# nrf52840-breakout-mdbt50q.net
KiCad netlist of a schematic drawn in EAGLE
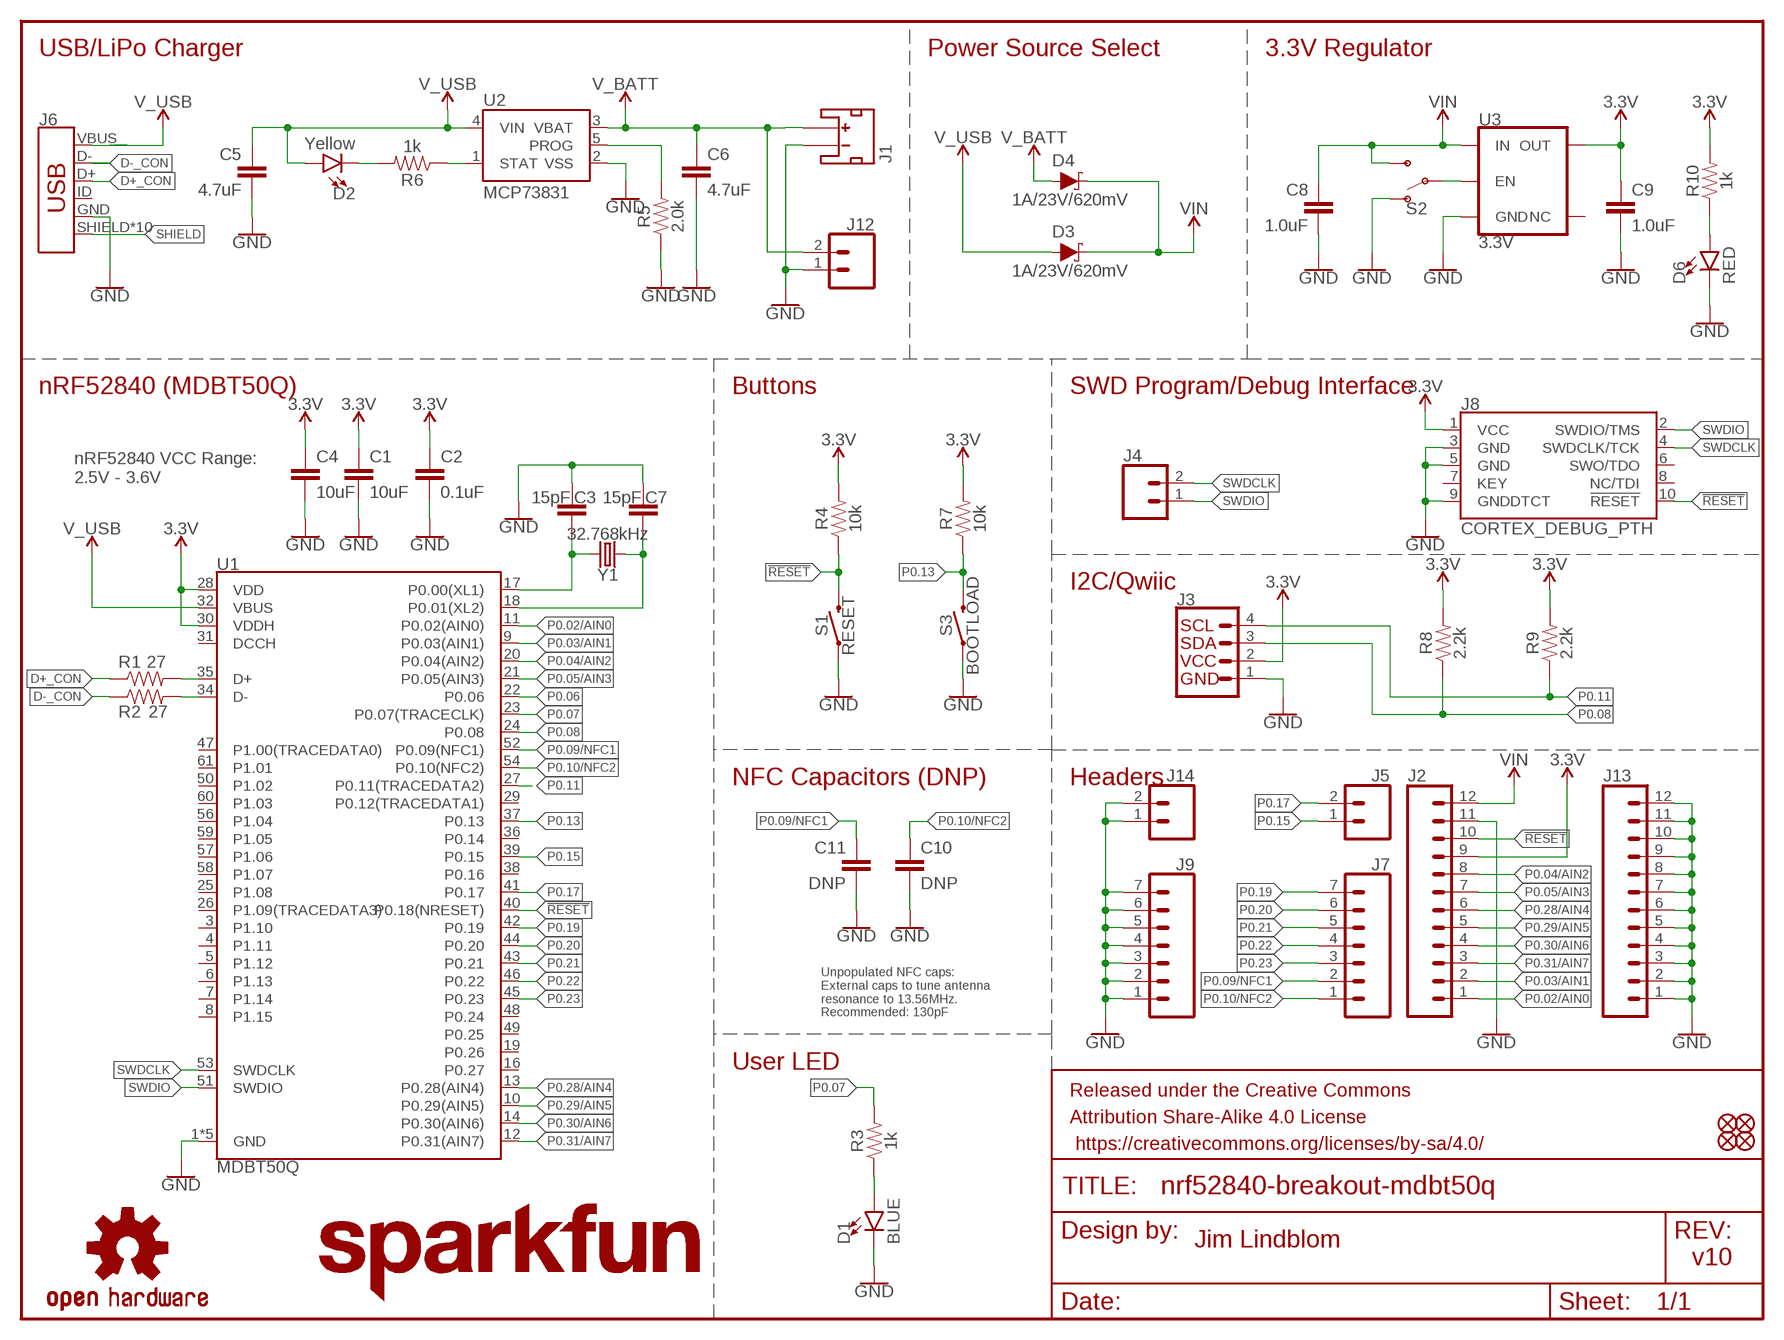
[diagram p0: schematic, sheet 1]

(export (version "E")
  (design (tool "Eeschema 10.0.6"))
  (components
    (comp (ref "C1")
      (value "10uF")
      (footprint "eagle-import:0603")
      (libsource (lib "eagle-import") (part "10UF-0603-6.3V-20%"))
    )
    (comp (ref "C2")
      (value "0.1uF")
      (footprint "eagle-import:0603")
      (libsource (lib "eagle-import") (part "0.1UF-0603-25V-(+80/-20%)"))
    )
    (comp (ref "C3")
      (value "15pF")
      (footprint "eagle-import:0603")
      (libsource (lib "eagle-import") (part "15PF-0603-50V-5%"))
    )
    (comp (ref "C4")
      (value "10uF")
      (footprint "eagle-import:0603")
      (libsource (lib "eagle-import") (part "10UF-0603-6.3V-20%"))
    )
    (comp (ref "C5")
      (value "4.7uF")
      (footprint "eagle-import:0603")
      (libsource (lib "eagle-import") (part "4.7UF-0603-6.3V-(10%)"))
    )
    (comp (ref "C6")
      (value "4.7uF")
      (footprint "eagle-import:0603")
      (libsource (lib "eagle-import") (part "4.7UF-0603-6.3V-(10%)"))
    )
    (comp (ref "C7")
      (value "15pF")
      (footprint "eagle-import:0603")
      (libsource (lib "eagle-import") (part "15PF-0603-50V-5%"))
    )
    (comp (ref "C8")
      (value "1.0uF")
      (footprint "eagle-import:0603")
      (libsource (lib "eagle-import") (part "1.0UF-0603-16V-10%"))
    )
    (comp (ref "C9")
      (value "1.0uF")
      (footprint "eagle-import:0603")
      (libsource (lib "eagle-import") (part "1.0UF-0603-16V-10%"))
    )
    (comp (ref "C10")
      (value "DNP")
      (footprint "eagle-import:0603")
      (libsource (lib "eagle-import") (part "270PF-0603-50V-5%"))
    )
    (comp (ref "C11")
      (value "DNP")
      (footprint "eagle-import:0603")
      (libsource (lib "eagle-import") (part "270PF-0603-50V-5%"))
    )
    (comp (ref "D1")
      (value "BLUE")
      (footprint "eagle-import:LED-0603")
      (libsource (lib "eagle-import") (part "LED-BLUE0603"))
    )
    (comp (ref "D2")
      (value "Yellow")
      (footprint "eagle-import:LED-0603")
      (libsource (lib "eagle-import") (part "LED-YELLOW0603"))
    )
    (comp (ref "D3")
      (value "1A/23V/620mV")
      (footprint "eagle-import:SOD-323")
      (libsource (lib "eagle-import") (part "DIODE-SCHOTTKY-BAT20J"))
    )
    (comp (ref "D4")
      (value "1A/23V/620mV")
      (footprint "eagle-import:SOD-323")
      (libsource (lib "eagle-import") (part "DIODE-SCHOTTKY-BAT20J"))
    )
    (comp (ref "D6")
      (value "RED")
      (footprint "eagle-import:LED-0603")
      (libsource (lib "eagle-import") (part "LED-RED0603"))
    )
    (comp (ref "FD1")
      (value "FIDUCIALUFIDUCIAL")
      (footprint "eagle-import:FIDUCIAL-MICRO")
      (libsource (lib "eagle-import") (part "FIDUCIALUFIDUCIAL"))
    )
    (comp (ref "FD2")
      (value "FIDUCIALUFIDUCIAL")
      (footprint "eagle-import:FIDUCIAL-MICRO")
      (libsource (lib "eagle-import") (part "FIDUCIALUFIDUCIAL"))
    )
    (comp (ref "FD3")
      (value "FIDUCIALUFIDUCIAL")
      (footprint "eagle-import:FIDUCIAL-MICRO")
      (libsource (lib "eagle-import") (part "FIDUCIALUFIDUCIAL"))
    )
    (comp (ref "FD4")
      (value "FIDUCIALUFIDUCIAL")
      (footprint "eagle-import:FIDUCIAL-MICRO")
      (libsource (lib "eagle-import") (part "FIDUCIALUFIDUCIAL"))
    )
    (comp (ref "FRAME1")
      (value "FRAME-LETTER")
      (footprint "eagle-import:CREATIVE_COMMONS")
      (libsource (lib "eagle-import") (part "FRAME-LETTER"))
    )
    (comp (ref "J1")
      (value "JST_2MM_MALESMD")
      (footprint "eagle-import:JST-2-SMD")
      (libsource (lib "eagle-import") (part "JST_2MM_MALESMD"))
    )
    (comp (ref "J2")
      (value "CONN_12NO_SILK")
      (footprint "eagle-import:1X12_NO_SILK")
      (libsource (lib "eagle-import") (part "CONN_12NO_SILK"))
    )
    (comp (ref "J3")
      (value "QWIIC_CONNECTORJS-1MM")
      (footprint "eagle-import:1X04_1MM_RA")
      (libsource (lib "eagle-import") (part "QWIIC_CONNECTORJS-1MM"))
    )
    (comp (ref "J4")
      (value "CONN_021X02_NO_SILK")
      (footprint "eagle-import:1X02_NO_SILK")
      (libsource (lib "eagle-import") (part "CONN_021X02_NO_SILK"))
    )
    (comp (ref "J5")
      (value "CONN_021X02_NO_SILK")
      (footprint "eagle-import:1X02_NO_SILK")
      (libsource (lib "eagle-import") (part "CONN_021X02_NO_SILK"))
    )
    (comp (ref "J6")
      (value "USB_MICRO-B_HALF_PTH_MILL")
      (footprint "eagle-import:USB-MICROB-PTH-MILL")
      (libsource (lib "eagle-import") (part "USB_MICRO-B_HALF_PTH_MILL"))
    )
    (comp (ref "J7")
      (value "CONN_07NO_SILK")
      (footprint "eagle-import:1X07_NO_SILK")
      (libsource (lib "eagle-import") (part "CONN_07NO_SILK"))
    )
    (comp (ref "J8")
      (value "CORTEX_DEBUG_PTH")
      (footprint "eagle-import:2X5-PTH-1.27MM")
      (libsource (lib "eagle-import") (part "CORTEX_DEBUG_PTH"))
    )
    (comp (ref "J9")
      (value "CONN_07NO_SILK")
      (footprint "eagle-import:1X07_NO_SILK")
      (libsource (lib "eagle-import") (part "CONN_07NO_SILK"))
    )
    (comp (ref "J12")
      (value "CONN_021X02_NO_SILK")
      (footprint "eagle-import:1X02_NO_SILK")
      (libsource (lib "eagle-import") (part "CONN_021X02_NO_SILK"))
    )
    (comp (ref "J13")
      (value "CONN_12NO_SILK")
      (footprint "eagle-import:1X12_NO_SILK")
      (libsource (lib "eagle-import") (part "CONN_12NO_SILK"))
    )
    (comp (ref "J14")
      (value "CONN_021X02_NO_SILK")
      (footprint "eagle-import:1X02_NO_SILK")
      (libsource (lib "eagle-import") (part "CONN_021X02_NO_SILK"))
    )
    (comp (ref "LOGO1")
      (value "SFE_LOGO_NAME.2_INCH")
      (footprint "eagle-import:SFE_LOGO_NAME_.2")
      (libsource (lib "eagle-import") (part "SFE_LOGO_NAME.2_INCH"))
    )
    (comp (ref "LOGO2")
      (value "OSHW-LOGOS")
      (footprint "eagle-import:OSHW-LOGO-S")
      (libsource (lib "eagle-import") (part "OSHW-LOGOS"))
    )
    (comp (ref "R1")
      (value "27")
      (footprint "eagle-import:0603")
      (libsource (lib "eagle-import") (part "27OHM-0603-1/10W-1%"))
    )
    (comp (ref "R2")
      (value "27")
      (footprint "eagle-import:0603")
      (libsource (lib "eagle-import") (part "27OHM-0603-1/10W-1%"))
    )
    (comp (ref "R3")
      (value "1k")
      (footprint "eagle-import:0603")
      (libsource (lib "eagle-import") (part "1KOHM-0603-1/10W-1%"))
    )
    (comp (ref "R4")
      (value "10k")
      (footprint "eagle-import:0603")
      (libsource (lib "eagle-import") (part "10KOHM-0603-1/10W-1%"))
    )
    (comp (ref "R5")
      (value "2.0k")
      (footprint "eagle-import:0603")
      (libsource (lib "eagle-import") (part "2.0KOHM-0603-1/10W-5%"))
    )
    (comp (ref "R6")
      (value "1k")
      (footprint "eagle-import:0603")
      (libsource (lib "eagle-import") (part "1KOHM-0603-1/10W-1%"))
    )
    (comp (ref "R7")
      (value "10k")
      (footprint "eagle-import:0603")
      (libsource (lib "eagle-import") (part "10KOHM-0603-1/10W-1%"))
    )
    (comp (ref "R8")
      (value "2.2k")
      (footprint "eagle-import:0603")
      (libsource (lib "eagle-import") (part "2.2KOHM-0603-1/10W-1%"))
    )
    (comp (ref "R9")
      (value "2.2k")
      (footprint "eagle-import:0603")
      (libsource (lib "eagle-import") (part "2.2KOHM-0603-1/10W-1%"))
    )
    (comp (ref "R10")
      (value "1k")
      (footprint "eagle-import:0603")
      (libsource (lib "eagle-import") (part "1KOHM-0603-1/10W-1%"))
    )
    (comp (ref "S1")
      (value "RESET")
      (footprint "eagle-import:TACTILE_SWITCH_SMD_RIGHT_ANGLE")
      (libsource (lib "eagle-import") (part "MOMENTARY-SWITCH-SPST-SMD-RIGHT-ANGLE"))
    )
    (comp (ref "S2")
      (value "SWITCH-SPDT-SMD-RIGHT-ANGLE")
      (footprint "eagle-import:SWITCH_SPST_SMD_A")
      (libsource (lib "eagle-import") (part "SWITCH-SPDT-SMD-RIGHT-ANGLE"))
    )
    (comp (ref "S3")
      (value "BOOTLOAD")
      (footprint "eagle-import:TACTILE_SWITCH_SMD_RIGHT_ANGLE")
      (libsource (lib "eagle-import") (part "MOMENTARY-SWITCH-SPST-SMD-RIGHT-ANGLE"))
    )
    (comp (ref "U1")
      (value "MDBT50Q")
      (footprint "eagle-import:MDBT50Q")
      (libsource (lib "eagle-import") (part "MDBT50Q"))
    )
    (comp (ref "U2")
      (value "MCP73831")
      (footprint "eagle-import:SOT23-5")
      (libsource (lib "eagle-import") (part "MCP73831"))
    )
    (comp (ref "U3")
      (value "3.3V")
      (footprint "eagle-import:SOT23-5")
      (libsource (lib "eagle-import") (part "V_REG_AP2112K-3.3V"))
    )
    (comp (ref "Y1")
      (value "32.768kHz")
      (footprint "eagle-import:CRYSTAL-SMD-3.2X1.5MM")
      (libsource (lib "eagle-import") (part "CRYSTAL-32.768KHZSMD-3.2X1.5"))
    )
  )
  (nets
    (net (code "1") (name "/~{RESET}") (class "Default")
      (node (ref "J2") (pin "10") (pinfunction "10_10") (pintype "passive"))
      (node (ref "J8") (pin "10") (pinfunction "~{RESET}_10") (pintype "bidirectional"))
      (node (ref "R4") (pin "1") (pinfunction "1_1") (pintype "passive"))
      (node (ref "S1") (pin "2") (pinfunction "2_2") (pintype "passive"))
      (node (ref "U1") (pin "40") (pinfunction "P0.18(NRESET)_40") (pintype "bidirectional"))
    )
    (net (code "2") (name "3.3V") (class "Default")
      (node (ref "C1") (pin "1") (pinfunction "1_1") (pintype "passive"))
      (node (ref "C2") (pin "1") (pinfunction "1_1") (pintype "passive"))
      (node (ref "C4") (pin "1") (pinfunction "1_1") (pintype "passive"))
      (node (ref "C9") (pin "1") (pinfunction "1_1") (pintype "passive"))
      (node (ref "J2") (pin "9") (pinfunction "9_9") (pintype "passive"))
      (node (ref "J3") (pin "2") (pinfunction "2_2") (pintype "power_in"))
      (node (ref "J8") (pin "1") (pinfunction "VCC_1") (pintype "bidirectional"))
      (node (ref "R10") (pin "2") (pinfunction "2_2") (pintype "passive"))
      (node (ref "R4") (pin "2") (pinfunction "2_2") (pintype "passive"))
      (node (ref "R7") (pin "2") (pinfunction "2_2") (pintype "passive"))
      (node (ref "R8") (pin "2") (pinfunction "2_2") (pintype "passive"))
      (node (ref "R9") (pin "2") (pinfunction "2_2") (pintype "passive"))
      (node (ref "U1") (pin "28") (pinfunction "VDD_28") (pintype "bidirectional"))
      (node (ref "U1") (pin "30") (pinfunction "VDDH_30") (pintype "bidirectional"))
      (node (ref "U3") (pin "5") (pinfunction "OUT_5") (pintype "passive"))
    )
    (net (code "3") (name "D+_CON") (class "Default")
      (node (ref "J6") (pin "D+") (pinfunction "D+_D+") (pintype "bidirectional"))
      (node (ref "R1") (pin "1") (pinfunction "1_1") (pintype "passive"))
    )
    (net (code "4") (name "D-_CON") (class "Default")
      (node (ref "J6") (pin "D-") (pinfunction "D-_D-") (pintype "bidirectional"))
      (node (ref "R2") (pin "1") (pinfunction "1_1") (pintype "passive"))
    )
    (net (code "5") (name "GND") (class "Default")
      (node (ref "C1") (pin "2") (pinfunction "2_2") (pintype "passive"))
      (node (ref "C10") (pin "2") (pinfunction "2_2") (pintype "passive"))
      (node (ref "C11") (pin "2") (pinfunction "2_2") (pintype "passive"))
      (node (ref "C2") (pin "2") (pinfunction "2_2") (pintype "passive"))
      (node (ref "C3") (pin "1") (pinfunction "1_1") (pintype "passive"))
      (node (ref "C4") (pin "2") (pinfunction "2_2") (pintype "passive"))
      (node (ref "C5") (pin "2") (pinfunction "2_2") (pintype "passive"))
      (node (ref "C6") (pin "2") (pinfunction "2_2") (pintype "passive"))
      (node (ref "C7") (pin "1") (pinfunction "1_1") (pintype "passive"))
      (node (ref "C8") (pin "2") (pinfunction "2_2") (pintype "passive"))
      (node (ref "C9") (pin "2") (pinfunction "2_2") (pintype "passive"))
      (node (ref "D1") (pin "C") (pinfunction "C_C") (pintype "passive"))
      (node (ref "D6") (pin "C") (pinfunction "C_C") (pintype "passive"))
      (node (ref "J1") (pin "1") (pinfunction "-_1") (pintype "bidirectional"))
      (node (ref "J12") (pin "1") (pinfunction "1_1") (pintype "passive"))
      (node (ref "J13") (pin "1") (pinfunction "1_1") (pintype "passive"))
      (node (ref "J13") (pin "10") (pinfunction "10_10") (pintype "passive"))
      (node (ref "J13") (pin "11") (pinfunction "11_11") (pintype "passive"))
      (node (ref "J13") (pin "12") (pinfunction "12_12") (pintype "passive"))
      (node (ref "J13") (pin "2") (pinfunction "2_2") (pintype "passive"))
      (node (ref "J13") (pin "3") (pinfunction "3_3") (pintype "passive"))
      (node (ref "J13") (pin "4") (pinfunction "4_4") (pintype "passive"))
      (node (ref "J13") (pin "5") (pinfunction "5_5") (pintype "passive"))
      (node (ref "J13") (pin "6") (pinfunction "6_6") (pintype "passive"))
      (node (ref "J13") (pin "7") (pinfunction "7_7") (pintype "passive"))
      (node (ref "J13") (pin "8") (pinfunction "8_8") (pintype "passive"))
      (node (ref "J13") (pin "9") (pinfunction "9_9") (pintype "passive"))
      (node (ref "J14") (pin "1") (pinfunction "1_1") (pintype "passive"))
      (node (ref "J14") (pin "2") (pinfunction "2_2") (pintype "passive"))
      (node (ref "J2") (pin "11") (pinfunction "11_11") (pintype "passive"))
      (node (ref "J3") (pin "1") (pinfunction "1_1") (pintype "power_in"))
      (node (ref "J6") (pin "GND") (pinfunction "GND_GND") (pintype "power_in"))
      (node (ref "J8") (pin "3") (pinfunction "GND_3") (pintype "bidirectional"))
      (node (ref "J8") (pin "5") (pinfunction "GND_5") (pintype "bidirectional"))
      (node (ref "J8") (pin "9") (pinfunction "GNDDTCT_9") (pintype "bidirectional"))
      (node (ref "J9") (pin "1") (pinfunction "1_1") (pintype "passive"))
      (node (ref "J9") (pin "2") (pinfunction "2_2") (pintype "passive"))
      (node (ref "J9") (pin "3") (pinfunction "3_3") (pintype "passive"))
      (node (ref "J9") (pin "4") (pinfunction "4_4") (pintype "passive"))
      (node (ref "J9") (pin "5") (pinfunction "5_5") (pintype "passive"))
      (node (ref "J9") (pin "6") (pinfunction "6_6") (pintype "passive"))
      (node (ref "J9") (pin "7") (pinfunction "7_7") (pintype "passive"))
      (node (ref "R5") (pin "1") (pinfunction "1_1") (pintype "passive"))
      (node (ref "S1") (pin "1") (pinfunction "1_1") (pintype "passive"))
      (node (ref "S2") (pin "1") (pinfunction "O_1") (pintype "passive"))
      (node (ref "S3") (pin "1") (pinfunction "1_1") (pintype "passive"))
      (node (ref "U1") (pin "1") (pinfunction "GND_1") (pintype "bidirectional"))
      (node (ref "U1") (pin "15") (pinfunction "GND_15") (pintype "bidirectional"))
      (node (ref "U1") (pin "2") (pinfunction "GND_2") (pintype "bidirectional"))
      (node (ref "U1") (pin "33") (pinfunction "GND_33") (pintype "bidirectional"))
      (node (ref "U1") (pin "55") (pinfunction "GND_55") (pintype "bidirectional"))
      (node (ref "U2") (pin "2") (pinfunction "VSS_2") (pintype "power_in"))
      (node (ref "U3") (pin "2") (pinfunction "GND_2") (pintype "input"))
    )
    (net (code "6") (name "Net-(D1-PadA)") (class "Default")
      (node (ref "D1") (pin "A") (pinfunction "A_A") (pintype "passive"))
      (node (ref "R3") (pin "1") (pinfunction "1_1") (pintype "passive"))
    )
    (net (code "7") (name "Net-(D2-PadC)") (class "Default")
      (node (ref "D2") (pin "C") (pinfunction "C_C") (pintype "passive"))
      (node (ref "R6") (pin "2") (pinfunction "2_2") (pintype "passive"))
    )
    (net (code "8") (name "Net-(D6-PadA)") (class "Default")
      (node (ref "D6") (pin "A") (pinfunction "A_A") (pintype "passive"))
      (node (ref "R10") (pin "1") (pinfunction "1_1") (pintype "passive"))
    )
    (net (code "9") (name "Net-(S2-P)") (class "Default")
      (node (ref "S2") (pin "2") (pinfunction "P_2") (pintype "passive"))
      (node (ref "U3") (pin "3") (pinfunction "EN_3") (pintype "input"))
    )
    (net (code "10") (name "Net-(U1-D+)") (class "Default")
      (node (ref "R1") (pin "2") (pinfunction "2_2") (pintype "passive"))
      (node (ref "U1") (pin "35") (pinfunction "D+_35") (pintype "bidirectional"))
    )
    (net (code "11") (name "Net-(U1-D-)") (class "Default")
      (node (ref "R2") (pin "2") (pinfunction "2_2") (pintype "passive"))
      (node (ref "U1") (pin "34") (pinfunction "D-_34") (pintype "bidirectional"))
    )
    (net (code "12") (name "Net-(U1-P0.00(XL1))") (class "Default")
      (node (ref "C3") (pin "2") (pinfunction "2_2") (pintype "passive"))
      (node (ref "U1") (pin "17") (pinfunction "P0.00(XL1)_17") (pintype "bidirectional"))
      (node (ref "Y1") (pin "P$2") (pinfunction "2_P$2") (pintype "passive"))
    )
    (net (code "13") (name "Net-(U1-P0.01(XL2))") (class "Default")
      (node (ref "C7") (pin "2") (pinfunction "2_2") (pintype "passive"))
      (node (ref "U1") (pin "18") (pinfunction "P0.01(XL2)_18") (pintype "bidirectional"))
      (node (ref "Y1") (pin "P$1") (pinfunction "1_P$1") (pintype "passive"))
    )
    (net (code "14") (name "Net-(U2-PROG)") (class "Default")
      (node (ref "R5") (pin "2") (pinfunction "2_2") (pintype "passive"))
      (node (ref "U2") (pin "5") (pinfunction "PROG_5") (pintype "input"))
    )
    (net (code "15") (name "Net-(U2-STAT)") (class "Default")
      (node (ref "R6") (pin "1") (pinfunction "1_1") (pintype "passive"))
      (node (ref "U2") (pin "1") (pinfunction "STAT_1") (pintype "output"))
    )
    (net (code "16") (name "P0.02{slash}AIN0") (class "Default")
      (node (ref "J2") (pin "1") (pinfunction "1_1") (pintype "passive"))
      (node (ref "U1") (pin "11") (pinfunction "P0.02(AIN0)_11") (pintype "bidirectional"))
    )
    (net (code "17") (name "P0.03{slash}AIN1") (class "Default")
      (node (ref "J2") (pin "2") (pinfunction "2_2") (pintype "passive"))
      (node (ref "U1") (pin "9") (pinfunction "P0.03(AIN1)_9") (pintype "bidirectional"))
    )
    (net (code "18") (name "P0.04{slash}AIN2") (class "Default")
      (node (ref "J2") (pin "8") (pinfunction "8_8") (pintype "passive"))
      (node (ref "U1") (pin "20") (pinfunction "P0.04(AIN2)_20") (pintype "bidirectional"))
    )
    (net (code "19") (name "P0.05{slash}AIN3") (class "Default")
      (node (ref "J2") (pin "7") (pinfunction "7_7") (pintype "passive"))
      (node (ref "U1") (pin "21") (pinfunction "P0.05(AIN3)_21") (pintype "bidirectional"))
    )
    (net (code "20") (name "P0.06") (class "Default")
      (node (ref "U1") (pin "22") (pinfunction "P0.06_22") (pintype "bidirectional"))
    )
    (net (code "21") (name "P0.07") (class "Default")
      (node (ref "R3") (pin "2") (pinfunction "2_2") (pintype "passive"))
      (node (ref "U1") (pin "23") (pinfunction "P0.07(TRACECLK)_23") (pintype "bidirectional"))
    )
    (net (code "22") (name "P0.08") (class "Default")
      (node (ref "J3") (pin "3") (pinfunction "3_3") (pintype "passive"))
      (node (ref "R8") (pin "1") (pinfunction "1_1") (pintype "passive"))
      (node (ref "U1") (pin "24") (pinfunction "P0.08_24") (pintype "bidirectional"))
    )
    (net (code "23") (name "P0.09{slash}NFC1") (class "Default")
      (node (ref "C11") (pin "1") (pinfunction "1_1") (pintype "passive"))
      (node (ref "J7") (pin "2") (pinfunction "2_2") (pintype "passive"))
      (node (ref "U1") (pin "52") (pinfunction "P0.09(NFC1)_52") (pintype "bidirectional"))
    )
    (net (code "24") (name "P0.10{slash}NFC2") (class "Default")
      (node (ref "C10") (pin "1") (pinfunction "1_1") (pintype "passive"))
      (node (ref "J7") (pin "1") (pinfunction "1_1") (pintype "passive"))
      (node (ref "U1") (pin "54") (pinfunction "P0.10(NFC2)_54") (pintype "bidirectional"))
    )
    (net (code "25") (name "P0.11") (class "Default")
      (node (ref "J3") (pin "4") (pinfunction "4_4") (pintype "passive"))
      (node (ref "R9") (pin "1") (pinfunction "1_1") (pintype "passive"))
      (node (ref "U1") (pin "27") (pinfunction "P0.11(TRACEDATA2)_27") (pintype "bidirectional"))
    )
    (net (code "26") (name "P0.13") (class "Default")
      (node (ref "R7") (pin "1") (pinfunction "1_1") (pintype "passive"))
      (node (ref "S3") (pin "2") (pinfunction "2_2") (pintype "passive"))
      (node (ref "U1") (pin "37") (pinfunction "P0.13_37") (pintype "bidirectional"))
    )
    (net (code "27") (name "P0.15") (class "Default")
      (node (ref "J5") (pin "1") (pinfunction "1_1") (pintype "passive"))
      (node (ref "U1") (pin "39") (pinfunction "P0.15_39") (pintype "bidirectional"))
    )
    (net (code "28") (name "P0.17") (class "Default")
      (node (ref "J5") (pin "2") (pinfunction "2_2") (pintype "passive"))
      (node (ref "U1") (pin "41") (pinfunction "P0.17_41") (pintype "bidirectional"))
    )
    (net (code "29") (name "P0.19") (class "Default")
      (node (ref "J7") (pin "7") (pinfunction "7_7") (pintype "passive"))
      (node (ref "U1") (pin "42") (pinfunction "P0.19_42") (pintype "bidirectional"))
    )
    (net (code "30") (name "P0.20") (class "Default")
      (node (ref "J7") (pin "6") (pinfunction "6_6") (pintype "passive"))
      (node (ref "U1") (pin "44") (pinfunction "P0.20_44") (pintype "bidirectional"))
    )
    (net (code "31") (name "P0.21") (class "Default")
      (node (ref "J7") (pin "5") (pinfunction "5_5") (pintype "passive"))
      (node (ref "U1") (pin "43") (pinfunction "P0.21_43") (pintype "bidirectional"))
    )
    (net (code "32") (name "P0.22") (class "Default")
      (node (ref "J7") (pin "4") (pinfunction "4_4") (pintype "passive"))
      (node (ref "U1") (pin "46") (pinfunction "P0.22_46") (pintype "bidirectional"))
    )
    (net (code "33") (name "P0.23") (class "Default")
      (node (ref "J7") (pin "3") (pinfunction "3_3") (pintype "passive"))
      (node (ref "U1") (pin "45") (pinfunction "P0.23_45") (pintype "bidirectional"))
    )
    (net (code "34") (name "P0.28{slash}AIN4") (class "Default")
      (node (ref "J2") (pin "6") (pinfunction "6_6") (pintype "passive"))
      (node (ref "U1") (pin "13") (pinfunction "P0.28(AIN4)_13") (pintype "bidirectional"))
    )
    (net (code "35") (name "P0.29{slash}AIN5") (class "Default")
      (node (ref "J2") (pin "5") (pinfunction "5_5") (pintype "passive"))
      (node (ref "U1") (pin "10") (pinfunction "P0.29(AIN5)_10") (pintype "bidirectional"))
    )
    (net (code "36") (name "P0.30{slash}AIN6") (class "Default")
      (node (ref "J2") (pin "4") (pinfunction "4_4") (pintype "passive"))
      (node (ref "U1") (pin "14") (pinfunction "P0.30(AIN6)_14") (pintype "bidirectional"))
    )
    (net (code "37") (name "P0.31{slash}AIN7") (class "Default")
      (node (ref "J2") (pin "3") (pinfunction "3_3") (pintype "passive"))
      (node (ref "U1") (pin "12") (pinfunction "P0.31(AIN7)_12") (pintype "bidirectional"))
    )
    (net (code "38") (name "SHIELD") (class "Default")
      (node (ref "J6") (pin "SHIELD") (pinfunction "SHIELD_SHIELD") (pintype "bidirectional"))
      (node (ref "J6") (pin "SHIELD10") (pinfunction "SHIELD_SHIELD10") (pintype "bidirectional"))
      (node (ref "J6") (pin "SHIELD2") (pinfunction "SHIELD_SHIELD2") (pintype "bidirectional"))
      (node (ref "J6") (pin "SHIELD3") (pinfunction "SHIELD_SHIELD3") (pintype "bidirectional"))
      (node (ref "J6") (pin "SHIELD4") (pinfunction "SHIELD_SHIELD4") (pintype "bidirectional"))
      (node (ref "J6") (pin "SHIELD5") (pinfunction "SHIELD_SHIELD5") (pintype "bidirectional"))
      (node (ref "J6") (pin "SHIELD6") (pinfunction "SHIELD_SHIELD6") (pintype "bidirectional"))
      (node (ref "J6") (pin "SHIELD7") (pinfunction "SHIELD_SHIELD7") (pintype "bidirectional"))
      (node (ref "J6") (pin "SHIELD8") (pinfunction "SHIELD_SHIELD8") (pintype "bidirectional"))
      (node (ref "J6") (pin "SHIELD9") (pinfunction "SHIELD_SHIELD9") (pintype "bidirectional"))
    )
    (net (code "39") (name "SWDCLK") (class "Default")
      (node (ref "J4") (pin "2") (pinfunction "2_2") (pintype "passive"))
      (node (ref "J8") (pin "4") (pinfunction "SWDCLK/TCK_4") (pintype "bidirectional"))
      (node (ref "U1") (pin "53") (pinfunction "SWDCLK_53") (pintype "bidirectional"))
    )
    (net (code "40") (name "SWDIO") (class "Default")
      (node (ref "J4") (pin "1") (pinfunction "1_1") (pintype "passive"))
      (node (ref "J8") (pin "2") (pinfunction "SWDIO/TMS_2") (pintype "bidirectional"))
      (node (ref "U1") (pin "51") (pinfunction "SWDIO_51") (pintype "bidirectional"))
    )
    (net (code "41") (name "VIN") (class "Default")
      (node (ref "C8") (pin "1") (pinfunction "1_1") (pintype "passive"))
      (node (ref "D3") (pin "C") (pinfunction "C_C") (pintype "passive"))
      (node (ref "D4") (pin "C") (pinfunction "C_C") (pintype "passive"))
      (node (ref "J2") (pin "12") (pinfunction "12_12") (pintype "passive"))
      (node (ref "S2") (pin "3") (pinfunction "S_3") (pintype "passive"))
      (node (ref "U3") (pin "1") (pinfunction "IN_1") (pintype "input"))
    )
    (net (code "42") (name "V_BATT") (class "Default")
      (node (ref "C6") (pin "1") (pinfunction "1_1") (pintype "passive"))
      (node (ref "D4") (pin "A") (pinfunction "A_A") (pintype "passive"))
      (node (ref "J1") (pin "2") (pinfunction "+_2") (pintype "bidirectional"))
      (node (ref "J12") (pin "2") (pinfunction "2_2") (pintype "passive"))
      (node (ref "U2") (pin "3") (pinfunction "VBAT_3") (pintype "power_in"))
    )
    (net (code "43") (name "V_USB") (class "Default")
      (node (ref "C5") (pin "1") (pinfunction "1_1") (pintype "passive"))
      (node (ref "D2") (pin "A") (pinfunction "A_A") (pintype "passive"))
      (node (ref "D3") (pin "A") (pinfunction "A_A") (pintype "passive"))
      (node (ref "J6") (pin "VBUS") (pinfunction "VBUS_VBUS") (pintype "power_in"))
      (node (ref "U1") (pin "32") (pinfunction "VBUS_32") (pintype "bidirectional"))
      (node (ref "U2") (pin "4") (pinfunction "VIN_4") (pintype "power_in"))
    )
    (net (code "44") (name "unconnected-(J6-PadID)") (class "Default")
      (node (ref "J6") (pin "ID") (pinfunction "ID_ID") (pintype "bidirectional"))
    )
    (net (code "45") (name "unconnected-(J8-KEY-Pad7)") (class "Default")
      (node (ref "J8") (pin "7") (pinfunction "KEY_7") (pintype "bidirectional"))
    )
    (net (code "46") (name "unconnected-(J8-NC{slash}TDI-Pad8)") (class "Default")
      (node (ref "J8") (pin "8") (pinfunction "NC/TDI_8") (pintype "bidirectional"))
    )
    (net (code "47") (name "unconnected-(J8-SWO{slash}TDO-Pad6)") (class "Default")
      (node (ref "J8") (pin "6") (pinfunction "SWO/TDO_6") (pintype "bidirectional"))
    )
    (net (code "48") (name "unconnected-(U1-DCCH-Pad31)") (class "Default")
      (node (ref "U1") (pin "31") (pinfunction "DCCH_31") (pintype "bidirectional"))
    )
    (net (code "49") (name "unconnected-(U1-P0.12(TRACEDATA1)-Pad29)") (class "Default")
      (node (ref "U1") (pin "29") (pinfunction "P0.12(TRACEDATA1)_29") (pintype "bidirectional"))
    )
    (net (code "50") (name "unconnected-(U1-P0.14-Pad36)") (class "Default")
      (node (ref "U1") (pin "36") (pinfunction "P0.14_36") (pintype "bidirectional"))
    )
    (net (code "51") (name "unconnected-(U1-P0.16-Pad38)") (class "Default")
      (node (ref "U1") (pin "38") (pinfunction "P0.16_38") (pintype "bidirectional"))
    )
    (net (code "52") (name "unconnected-(U1-P0.24-Pad48)") (class "Default")
      (node (ref "U1") (pin "48") (pinfunction "P0.24_48") (pintype "bidirectional"))
    )
    (net (code "53") (name "unconnected-(U1-P0.25-Pad49)") (class "Default")
      (node (ref "U1") (pin "49") (pinfunction "P0.25_49") (pintype "bidirectional"))
    )
    (net (code "54") (name "unconnected-(U1-P0.26-Pad19)") (class "Default")
      (node (ref "U1") (pin "19") (pinfunction "P0.26_19") (pintype "bidirectional"))
    )
    (net (code "55") (name "unconnected-(U1-P0.27-Pad16)") (class "Default")
      (node (ref "U1") (pin "16") (pinfunction "P0.27_16") (pintype "bidirectional"))
    )
    (net (code "56") (name "unconnected-(U1-P1.00(TRACEDATA0)-Pad47)") (class "Default")
      (node (ref "U1") (pin "47") (pinfunction "P1.00(TRACEDATA0)_47") (pintype "bidirectional"))
    )
    (net (code "57") (name "unconnected-(U1-P1.01-Pad61)") (class "Default")
      (node (ref "U1") (pin "61") (pinfunction "P1.01_61") (pintype "bidirectional"))
    )
    (net (code "58") (name "unconnected-(U1-P1.02-Pad50)") (class "Default")
      (node (ref "U1") (pin "50") (pinfunction "P1.02_50") (pintype "bidirectional"))
    )
    (net (code "59") (name "unconnected-(U1-P1.03-Pad60)") (class "Default")
      (node (ref "U1") (pin "60") (pinfunction "P1.03_60") (pintype "bidirectional"))
    )
    (net (code "60") (name "unconnected-(U1-P1.04-Pad56)") (class "Default")
      (node (ref "U1") (pin "56") (pinfunction "P1.04_56") (pintype "bidirectional"))
    )
    (net (code "61") (name "unconnected-(U1-P1.05-Pad59)") (class "Default")
      (node (ref "U1") (pin "59") (pinfunction "P1.05_59") (pintype "bidirectional"))
    )
    (net (code "62") (name "unconnected-(U1-P1.06-Pad57)") (class "Default")
      (node (ref "U1") (pin "57") (pinfunction "P1.06_57") (pintype "bidirectional"))
    )
    (net (code "63") (name "unconnected-(U1-P1.07-Pad58)") (class "Default")
      (node (ref "U1") (pin "58") (pinfunction "P1.07_58") (pintype "bidirectional"))
    )
    (net (code "64") (name "unconnected-(U1-P1.08-Pad25)") (class "Default")
      (node (ref "U1") (pin "25") (pinfunction "P1.08_25") (pintype "bidirectional"))
    )
    (net (code "65") (name "unconnected-(U1-P1.09(TRACEDATA3)-Pad26)") (class "Default")
      (node (ref "U1") (pin "26") (pinfunction "P1.09(TRACEDATA3)_26") (pintype "bidirectional"))
    )
    (net (code "66") (name "unconnected-(U1-P1.10-Pad3)") (class "Default")
      (node (ref "U1") (pin "3") (pinfunction "P1.10_3") (pintype "bidirectional"))
    )
    (net (code "67") (name "unconnected-(U1-P1.11-Pad4)") (class "Default")
      (node (ref "U1") (pin "4") (pinfunction "P1.11_4") (pintype "bidirectional"))
    )
    (net (code "68") (name "unconnected-(U1-P1.12-Pad5)") (class "Default")
      (node (ref "U1") (pin "5") (pinfunction "P1.12_5") (pintype "bidirectional"))
    )
    (net (code "69") (name "unconnected-(U1-P1.13-Pad6)") (class "Default")
      (node (ref "U1") (pin "6") (pinfunction "P1.13_6") (pintype "bidirectional"))
    )
    (net (code "70") (name "unconnected-(U1-P1.14-Pad7)") (class "Default")
      (node (ref "U1") (pin "7") (pinfunction "P1.14_7") (pintype "bidirectional"))
    )
    (net (code "71") (name "unconnected-(U1-P1.15-Pad8)") (class "Default")
      (node (ref "U1") (pin "8") (pinfunction "P1.15_8") (pintype "bidirectional"))
    )
    (net (code "72") (name "unconnected-(U3-NC-Pad4)") (class "Default")
      (node (ref "U3") (pin "4") (pinfunction "NC_4") (pintype "no_connect"))
    )
  )
)
